# RF.net
KiCad netlist of a schematic drawn in Altium Designer
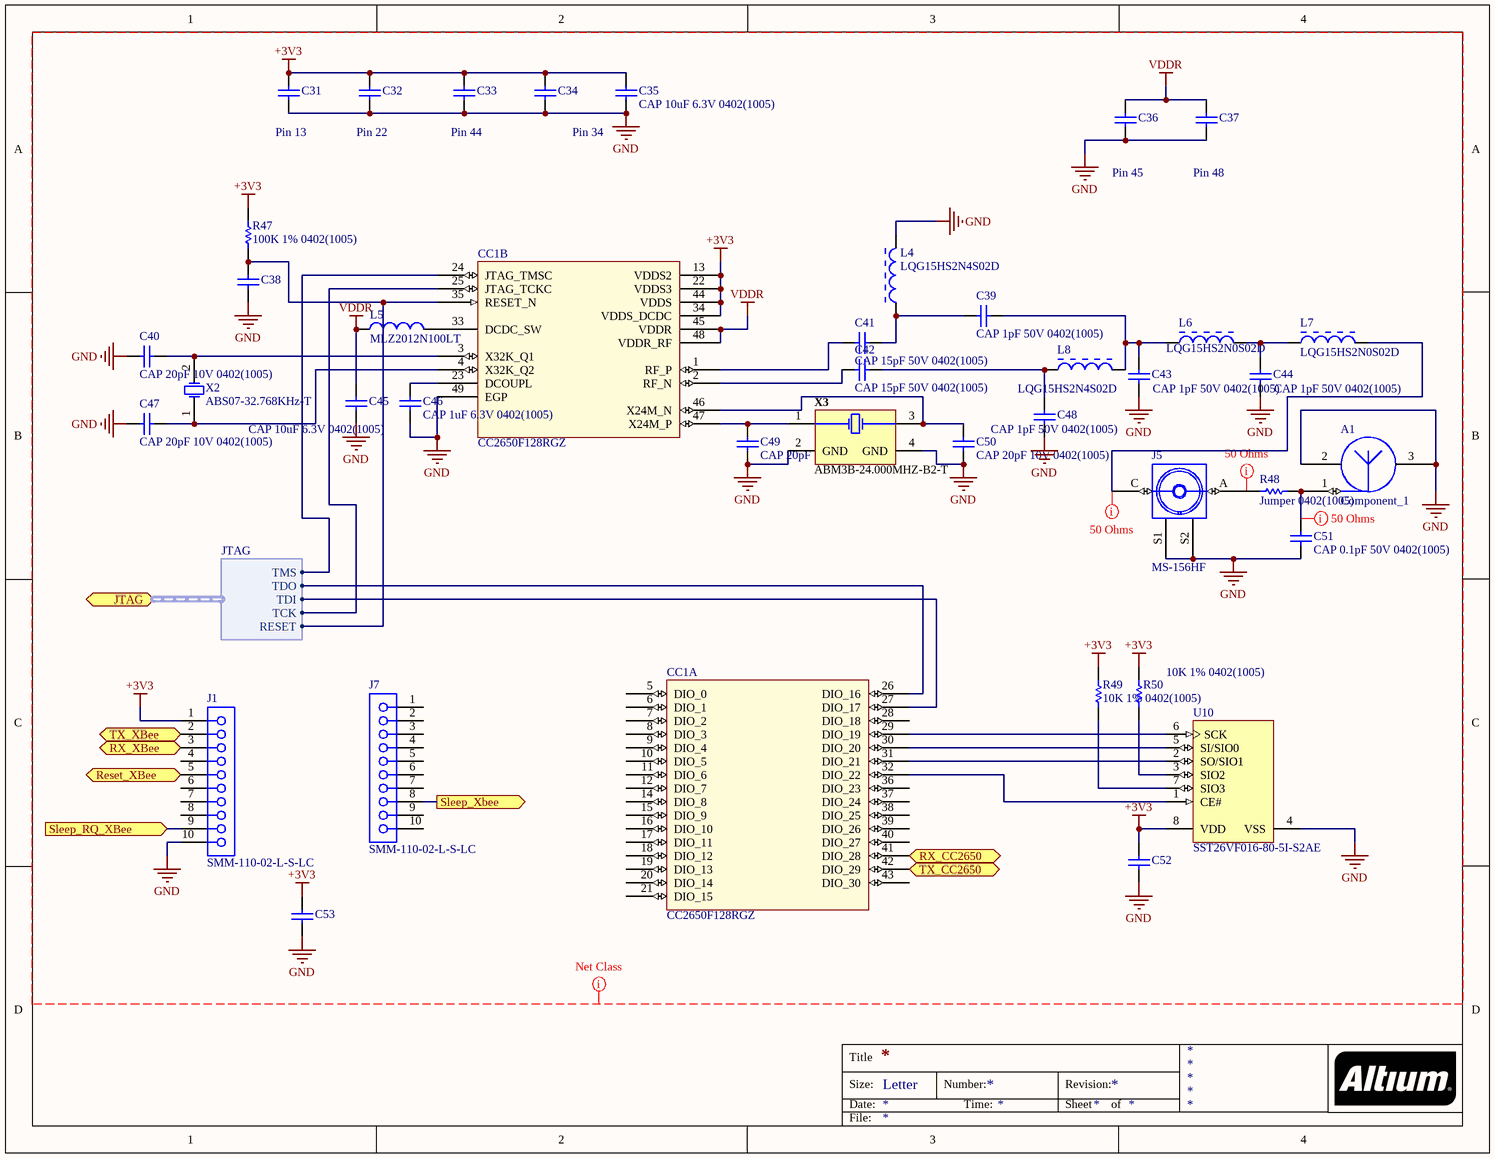
[diagram p0: RF.SchDoc]

(export (version "E")
  (design (tool "Eeschema 10.0.6"))
  (components
    (comp (ref "A1")
      (value "Component_1")
      (footprint "Microstrip Antenna")
      (libsource (lib "Antenna") (part "Component_1"))
    )
    (comp (ref "C31")
      (value "CAP 100nF 10V 0402(1005)")
      (footprint "CAPC0402(1005)60_L")
      (description "CAP 100nF 10V ±20% 0402 (1005 Metric) Thickness 0.6mm SMD")
      (fields (field (name "TOLERANCE") "Â±20%"))
      (libsource (lib "Altium Content Vault") (part "CAP"))
    )
    (comp (ref "C32")
      (value "CAP 100nF 10V 0402(1005)")
      (footprint "CAPC0402(1005)60_L")
      (description "CAP 100nF 10V ±20% 0402 (1005 Metric) Thickness 0.6mm SMD")
      (fields (field (name "TOLERANCE") "Â±20%"))
      (libsource (lib "Altium Content Vault") (part "CAP"))
    )
    (comp (ref "C33")
      (value "CAP 100nF 10V 0402(1005)")
      (footprint "CAPC0402(1005)60_L")
      (description "CAP 100nF 10V ±20% 0402 (1005 Metric) Thickness 0.6mm SMD")
      (fields (field (name "TOLERANCE") "Â±20%"))
      (libsource (lib "Altium Content Vault") (part "CAP"))
    )
    (comp (ref "C34")
      (value "CAP 100nF 10V 0402(1005)")
      (footprint "CAPC0402(1005)60_L")
      (description "CAP 100nF 10V ±20% 0402 (1005 Metric) Thickness 0.6mm SMD")
      (fields (field (name "TOLERANCE") "Â±20%"))
      (libsource (lib "Altium Content Vault") (part "CAP"))
    )
    (comp (ref "C35")
      (value "CAP 10uF 6.3V 0402(1005)")
      (footprint "CAPC0402(1005)60_L")
      (description "CAP 10uF 6.3V ±20% 0402 (1005 Metric) Thickness 0.6mm SMD")
      (fields (field (name "TOLERANCE") "Â±20%"))
      (libsource (lib "Altium Content Vault") (part "CAP"))
    )
    (comp (ref "C36")
      (value "CAP 100nF 10V 0402(1005)")
      (footprint "CAPC0402(1005)60_L")
      (description "CAP 100nF 10V ±20% 0402 (1005 Metric) Thickness 0.6mm SMD")
      (fields (field (name "TOLERANCE") "Â±20%"))
      (libsource (lib "Altium Content Vault") (part "CAP"))
    )
    (comp (ref "C37")
      (value "CAP 100nF 10V 0402(1005)")
      (footprint "CAPC0402(1005)60_L")
      (description "CAP 100nF 10V ±20% 0402 (1005 Metric) Thickness 0.6mm SMD")
      (fields (field (name "TOLERANCE") "Â±20%"))
      (libsource (lib "Altium Content Vault") (part "CAP"))
    )
    (comp (ref "C38")
      (value "CAP 100nF 10V 0402(1005)")
      (footprint "CAPC0402(1005)60_L")
      (description "CAP 100nF 10V ±20% 0402 (1005 Metric) Thickness 0.6mm SMD")
      (fields (field (name "TOLERANCE") "Â±20%"))
      (libsource (lib "Altium Content Vault") (part "CAP"))
    )
    (comp (ref "C39")
      (value "CAP 1pF 50V 0402(1005)")
      (footprint "CAPC0402(1005)33_L")
      (description "CAP 1pF 50V ±0.25pF 0402 (1005 Metric) Thickness 0.33mm SMD")
      (fields (field (name "TOLERANCE") "Â±0.25pF"))
      (libsource (lib "Altium Content Vault") (part "CMP-1034-00058-1"))
    )
    (comp (ref "C40")
      (value "CAP 20pF 10V 0402(1005)")
      (footprint "CAPC0402(1005)60_L")
      (description "CAP 20pF 10V ±5% 0402 (1005 Metric) Thickness 0.6mm SMD")
      (fields (field (name "TOLERANCE") "Â±5%"))
      (libsource (lib "Altium Content Vault") (part "CAP"))
    )
    (comp (ref "C41")
      (value "CAP 15pF 50V 0402(1005)")
      (footprint "CAPC0402(1005)33_L")
      (description "CAP 15pF 50V ±5% 0402 (1005 Metric) Thickness 0.33mm SMD")
      (fields (field (name "TOLERANCE") "Â±5%"))
      (libsource (lib "Altium Content Vault") (part "CMP-1034-00814-1"))
    )
    (comp (ref "C42")
      (value "CAP 15pF 50V 0402(1005)")
      (footprint "CAPC0402(1005)33_L")
      (description "CAP 15pF 50V ±5% 0402 (1005 Metric) Thickness 0.33mm SMD")
      (fields (field (name "TOLERANCE") "Â±5%"))
      (libsource (lib "Altium Content Vault") (part "CMP-1034-00814-1"))
    )
    (comp (ref "C43")
      (value "CAP 1pF 50V 0402(1005)")
      (footprint "CAPC0402(1005)33_L")
      (description "CAP 1pF 50V ±0.25pF 0402 (1005 Metric) Thickness 0.33mm SMD")
      (fields (field (name "TOLERANCE") "Â±0.25pF"))
      (libsource (lib "Altium Content Vault") (part "CMP-1034-00058-1"))
    )
    (comp (ref "C44")
      (value "CAP 1pF 50V 0402(1005)")
      (footprint "CAPC0402(1005)33_L")
      (description "CAP 1pF 50V ±0.25pF 0402 (1005 Metric) Thickness 0.33mm SMD")
      (fields (field (name "TOLERANCE") "Â±0.25pF"))
      (libsource (lib "Altium Content Vault") (part "CMP-1034-00058-1"))
    )
    (comp (ref "C45")
      (value "CAP 10uF 6.3V 0402(1005)")
      (footprint "CAPC0402(1005)60_L")
      (description "CAP 10uF 6.3V ±20% 0402 (1005 Metric) Thickness 0.6mm SMD")
      (fields (field (name "TOLERANCE") "Â±20%"))
      (libsource (lib "Altium Content Vault") (part "CMP-1034-02138-1"))
    )
    (comp (ref "C46")
      (value "CAP 1uF 6.3V 0402(1005)")
      (footprint "CAPC0402(1005)60_L")
      (description "CAP 1uF 6.3V -20% to +80% 0402 (1005 Metric) Thickness 0.6mm SMD")
      (fields (field (name "TOLERANCE") "-20% to +80%"))
      (libsource (lib "Altium Content Vault") (part "CAP"))
    )
    (comp (ref "C47")
      (value "CAP 20pF 10V 0402(1005)")
      (footprint "CAPC0402(1005)60_L")
      (description "CAP 20pF 10V ±5% 0402 (1005 Metric) Thickness 0.6mm SMD")
      (fields (field (name "TOLERANCE") "Â±5%"))
      (libsource (lib "Altium Content Vault") (part "CAP"))
    )
    (comp (ref "C48")
      (value "CAP 1pF 50V 0402(1005)")
      (footprint "CAPC0402(1005)33_L")
      (description "CAP 1pF 50V ±0.25pF 0402 (1005 Metric) Thickness 0.33mm SMD")
      (fields (field (name "TOLERANCE") "Â±0.25pF"))
      (libsource (lib "Altium Content Vault") (part "CMP-1034-00058-1"))
    )
    (comp (ref "C49")
      (value "CAP 20pF 10V 0402(1005)")
      (footprint "CAPC0402(1005)60_L")
      (description "CAP 20pF 10V ±5% 0402 (1005 Metric) Thickness 0.6mm SMD")
      (fields (field (name "TOLERANCE") "Â±5%"))
      (libsource (lib "Altium Content Vault") (part "CMP-1034-00874-1"))
    )
    (comp (ref "C50")
      (value "CAP 20pF 10V 0402(1005)")
      (footprint "CAPC0402(1005)60_L")
      (description "CAP 20pF 10V ±5% 0402 (1005 Metric) Thickness 0.6mm SMD")
      (fields (field (name "TOLERANCE") "Â±5%"))
      (libsource (lib "Altium Content Vault") (part "CMP-1034-00874-1"))
    )
    (comp (ref "C51")
      (value "CAP 0.1pF 50V 0402(1005)")
      (footprint "CAPC0402(1005)33_L")
      (description "CAP 0.1pF 50V ±0.1pF 0402 (1005 Metric) Thickness 0.33mm SMD")
      (fields (field (name "TOLERANCE") "Â±0.1pF"))
      (libsource (lib "Altium Content Vault") (part "CMP-1034-00002-1"))
    )
    (comp (ref "C52")
      (value "CAP 100nF 10V 0402(1005)")
      (footprint "CAPC0402(1005)60_L")
      (description "CAP 100nF 10V ±20% 0402 (1005 Metric) Thickness 0.6mm SMD")
      (fields (field (name "TOLERANCE") "Â±20%"))
      (libsource (lib "Altium Content Vault") (part "CAP"))
    )
    (comp (ref "C53")
      (value "CAP 100nF 10V 0402(1005)")
      (footprint "CAPC0402(1005)60_L")
      (description "CAP 100nF 10V ±20% 0402 (1005 Metric) Thickness 0.6mm SMD")
      (fields (field (name "TOLERANCE") "Â±20%"))
      (libsource (lib "Altium Content Vault") (part "CMP-1034-02066-1"))
    )
    (comp (ref "CC1")
      (value "CC2650F128RGZ")
      (footprint "RGZ48-4100X4100TP")
      (description "RF Microcontrollers - MCU SimpleLink multi-std Wireless MCU 2.4Ghz")
      (fields
        (field (name "MANUFACTURER") "Texas Instruments")
        (field (name "MANUFACTURER PART NUMBER") "CC2650F128RGZT")
      )
      (libsource (lib "CERN PCB Vault") (part "CC2650 7x7"))
    )
    (comp (ref "J1")
      (value "SMM-110-02-L-S-LC")
      (footprint "SMTC-SMM-110-02-X-S-LC")
      (fields (field (name "MANUFACTURER") "Samtec"))
      (libsource (lib "Altium Content Vault") (part "CMP-1022-00175-1"))
    )
    (comp (ref "J5")
      (value "MS-156HF")
      (footprint "MS-156HF")
      (description "Subminiature Coaxial Swtich, 1.6mm High, DC - 6GHz")
      (libsource (lib "MS-156HF") (part "MS-156HF"))
    )
    (comp (ref "J7")
      (value "SMM-110-02-L-S-LC")
      (footprint "SMTC-SMM-110-02-X-S-LC")
      (fields (field (name "MANUFACTURER") "Samtec"))
      (libsource (lib "Altium Content Vault") (part "CMP-1022-00175-1"))
    )
    (comp (ref "L4")
      (value "LQG15HS2N4S02D")
      (footprint "MURA-IND0402_V")
      (fields (field (name "MANUFACTURER") "Murata"))
      (libsource (lib "Altium Content Vault") (part "CMP-0499-00001-3"))
    )
    (comp (ref "L5")
      (value "MLZ2012N100LT")
      (footprint "TDK-IND0805-125_V")
      (description "Multilayer Inductor, 10 uH, ±20%, 300 mOhm, 50MHz, 0805(2012)")
      (libsource (lib "Altium Content Vault") (part "CMP-0266-00001-1"))
    )
    (comp (ref "L6")
      (value "LQG15HS2N0S02D")
      (footprint "MURA-IND0402_V")
      (fields (field (name "MANUFACTURER") "Murata"))
      (libsource (lib "Altium Content Vault") (part "MURA-INDC-2"))
    )
    (comp (ref "L7")
      (value "LQG15HS2N0S02D")
      (footprint "MURA-IND0402_V")
      (fields (field (name "MANUFACTURER") "Murata"))
      (libsource (lib "Altium Content Vault") (part "MURA-INDC-2"))
    )
    (comp (ref "L8")
      (value "LQG15HS2N4S02D")
      (footprint "MURA-IND0402_V")
      (fields (field (name "MANUFACTURER") "Murata"))
      (libsource (lib "Altium Content Vault") (part "CMP-0499-00001-3"))
    )
    (comp (ref "R47")
      (value "100K 1% 0402(1005)")
      (footprint "RESC0402(1005)_L")
      (description "100K 0.063W 1% 0402 (1005 Metric)  SMD")
      (fields (field (name "POWER") "0.063 W") (field (name "TOLERANCE") "1 %"))
      (libsource (lib "Altium Content Vault") (part "RES"))
    )
    (comp (ref "R48")
      (value "Jumper 0402(1005)")
      (footprint "RESC0402(1005)_L")
      (description "Jumper 0402 (1005 Metric)")
      (fields (field (name "TOLERANCE") "None"))
      (libsource (lib "Altium Content Vault") (part "RES"))
    )
    (comp (ref "R49")
      (value "10K 1% 0402(1005)")
      (footprint "RESC0402(1005)_L")
      (description "10K 0.063W 1% 0402 (1005 Metric)  SMD")
      (fields (field (name "TOLERANCE") "1 %") (field (name "POWER") "0.063 W"))
      (libsource (lib "Altium Content Vault") (part "RES"))
    )
    (comp (ref "R50")
      (value "10K 1% 0402(1005)")
      (footprint "RESC0402(1005)_L")
      (description "10K 0.063W 1% 0402 (1005 Metric)  SMD")
      (fields (field (name "TOLERANCE") "1 %") (field (name "POWER") "0.063 W"))
      (libsource (lib "Altium Content Vault") (part "RES"))
    )
    (comp (ref "U10")
      (value "SST26VF016-80-5I-S2AE")
      (footprint "MCHP-SOIC-S2A8_L")
      (fields (field (name "MANUFACTURER") "Microchip"))
      (libsource (lib "Altium Content Vault") (part "MCHP-SST26VFXXX-SOIJ-8"))
    )
    (comp (ref "X2")
      (value "ABS07-32.768KHz-T")
      (footprint "ABRA-ABS07-2_V")
      (description "Crystal, 32.768 kHz, 12.5 pF, -40 to 85 degC, SMD Low Profile 3.2 x 1.5 x 0.9 mm, Tape and Reel")
      (fields (field (name "MANUFACTURER") "Abracon"))
      (libsource (lib "Altium Content Vault") (part "CMP-0447-00001-2"))
    )
    (comp (ref "X3")
      (value "ABM3B-24.000MHZ-B2-T")
      (footprint "ABRA-ABM3B-4_V")
      (description "Ceramic SMD Crystal, 24 MHz, +/- 20 ppm, 50 Ohm, -20 to 70 degC, 4-Pin SMD, RoHS, Tape and Reel")
      (libsource (lib "Altium Content Vault") (part "CMP-1688-00008-1"))
    )
  )
  (nets
    (net (code "2") (name "+3V3") (class "Default")
      (node (ref "C31") (pin "2") (pinfunction "2_2") (pintype "passive"))
      (node (ref "C32") (pin "2") (pinfunction "2_2") (pintype "passive"))
      (node (ref "C33") (pin "2") (pinfunction "2_2") (pintype "passive"))
      (node (ref "C34") (pin "2") (pinfunction "2_2") (pintype "passive"))
      (node (ref "C35") (pin "2") (pinfunction "2_2") (pintype "passive"))
      (node (ref "C52") (pin "2") (pinfunction "2_2") (pintype "passive"))
      (node (ref "C53") (pin "2") (pinfunction "2_2") (pintype "passive"))
      (node (ref "CC1") (pin "13") (pinfunction "VDDS2_13") (pintype "power_in"))
      (node (ref "CC1") (pin "22") (pinfunction "VDDS3_22") (pintype "power_in"))
      (node (ref "CC1") (pin "34") (pinfunction "VDDS_DCDC_34") (pintype "power_in"))
      (node (ref "CC1") (pin "44") (pinfunction "VDDS_44") (pintype "power_in"))
      (node (ref "J1") (pin "1") (pinfunction "1_1") (pintype "passive"))
      (node (ref "R47") (pin "2") (pinfunction "2_2") (pintype "passive"))
      (node (ref "R49") (pin "2") (pinfunction "2_2") (pintype "passive"))
      (node (ref "R50") (pin "2") (pinfunction "2_2") (pintype "passive"))
      (node (ref "U10") (pin "8") (pinfunction "VDD_8") (pintype "power_in"))
    )
    (net (code "3") (name "/RESET") (class "Default")
      (node (ref "C38") (pin "2") (pinfunction "2_2") (pintype "passive"))
      (node (ref "CC1") (pin "35") (pinfunction "RESET_N_35") (pintype "input"))
      (node (ref "R47") (pin "1") (pinfunction "1_1") (pintype "passive"))
    )
    (net (code "4") (name "/RX_CC2650") (class "Default")
      (node (ref "CC1") (pin "41") (pinfunction "DIO_28_41") (pintype "bidirectional"))
    )
    (net (code "5") (name "/RX_XBee") (class "Default")
      (node (ref "J1") (pin "3") (pinfunction "3_3") (pintype "passive"))
    )
    (net (code "6") (name "/Reset_XBee") (class "Default")
      (node (ref "J1") (pin "5") (pinfunction "5_5") (pintype "passive"))
    )
    (net (code "7") (name "/Sleep_RQ_XBee") (class "Default")
      (node (ref "J1") (pin "9") (pinfunction "9_9") (pintype "passive"))
    )
    (net (code "8") (name "/Sleep_Xbee") (class "Default")
      (node (ref "J7") (pin "8") (pinfunction "8_8") (pintype "passive"))
    )
    (net (code "9") (name "/TCK") (class "Default")
      (node (ref "CC1") (pin "25") (pinfunction "JTAG_TCKC_25") (pintype "bidirectional"))
    )
    (net (code "10") (name "/TDI") (class "Default")
      (node (ref "CC1") (pin "27") (pinfunction "DIO_17_27") (pintype "bidirectional"))
    )
    (net (code "11") (name "/TDO") (class "Default")
      (node (ref "CC1") (pin "26") (pinfunction "DIO_16_26") (pintype "bidirectional"))
    )
    (net (code "12") (name "/TMS") (class "Default")
      (node (ref "CC1") (pin "24") (pinfunction "JTAG_TMSC_24") (pintype "bidirectional"))
    )
    (net (code "13") (name "/TX_CC2650") (class "Default")
      (node (ref "CC1") (pin "42") (pinfunction "DIO_29_42") (pintype "bidirectional"))
    )
    (net (code "14") (name "/TX_XBee") (class "Default")
      (node (ref "J1") (pin "2") (pinfunction "2_2") (pintype "passive"))
    )
    (net (code "16") (name "GND") (class "Default")
      (node (ref "A1") (pin "2") (pinfunction "2_2") (pintype "power_in"))
      (node (ref "A1") (pin "3") (pinfunction "3_3") (pintype "power_in"))
      (node (ref "C31") (pin "1") (pinfunction "1_1") (pintype "passive"))
      (node (ref "C32") (pin "1") (pinfunction "1_1") (pintype "passive"))
      (node (ref "C33") (pin "1") (pinfunction "1_1") (pintype "passive"))
      (node (ref "C34") (pin "1") (pinfunction "1_1") (pintype "passive"))
      (node (ref "C35") (pin "1") (pinfunction "1_1") (pintype "passive"))
      (node (ref "C36") (pin "1") (pinfunction "1_1") (pintype "passive"))
      (node (ref "C37") (pin "1") (pinfunction "1_1") (pintype "passive"))
      (node (ref "C38") (pin "1") (pinfunction "1_1") (pintype "passive"))
      (node (ref "C40") (pin "1") (pinfunction "1_1") (pintype "passive"))
      (node (ref "C43") (pin "1") (pinfunction "1_1") (pintype "passive"))
      (node (ref "C44") (pin "1") (pinfunction "1_1") (pintype "passive"))
      (node (ref "C45") (pin "1") (pinfunction "1_1") (pintype "passive"))
      (node (ref "C46") (pin "1") (pinfunction "1_1") (pintype "passive"))
      (node (ref "C47") (pin "1") (pinfunction "1_1") (pintype "passive"))
      (node (ref "C48") (pin "1") (pinfunction "1_1") (pintype "passive"))
      (node (ref "C49") (pin "2") (pinfunction "2_2") (pintype "passive"))
      (node (ref "C50") (pin "2") (pinfunction "2_2") (pintype "passive"))
      (node (ref "C51") (pin "1") (pinfunction "1_1") (pintype "passive"))
      (node (ref "C52") (pin "1") (pinfunction "1_1") (pintype "passive"))
      (node (ref "C53") (pin "1") (pinfunction "1_1") (pintype "passive"))
      (node (ref "CC1") (pin "49") (pinfunction "EGP_49") (pintype "power_in"))
      (node (ref "J1") (pin "10") (pinfunction "10_10") (pintype "passive"))
      (node (ref "J5") (pin "S1") (pinfunction "S1_S1") (pintype "power_in"))
      (node (ref "J5") (pin "S2") (pinfunction "S2_S2") (pintype "power_in"))
      (node (ref "L4") (pin "2") (pinfunction "2_2") (pintype "passive"))
      (node (ref "U10") (pin "4") (pinfunction "VSS_4") (pintype "power_in"))
      (node (ref "X3") (pin "2") (pinfunction "GND_2") (pintype "power_in"))
      (node (ref "X3") (pin "4") (pinfunction "GND_4") (pintype "power_in"))
    )
    (net (code "17") (name "Net-(A1-Pad1)") (class "Default")
      (node (ref "A1") (pin "1") (pinfunction "1_1") (pintype "bidirectional"))
      (node (ref "C51") (pin "2") (pinfunction "2_2") (pintype "passive"))
      (node (ref "R48") (pin "2") (pinfunction "2_2") (pintype "passive"))
    )
    (net (code "18") (name "Net-(C39-Pad1)") (class "Default")
      (node (ref "C39") (pin "1") (pinfunction "1_1") (pintype "passive"))
      (node (ref "C41") (pin "2") (pinfunction "2_2") (pintype "passive"))
      (node (ref "L4") (pin "1") (pinfunction "1_1") (pintype "passive"))
    )
    (net (code "19") (name "Net-(C39-Pad2)") (class "Default")
      (node (ref "C39") (pin "2") (pinfunction "2_2") (pintype "passive"))
      (node (ref "C43") (pin "2") (pinfunction "2_2") (pintype "passive"))
      (node (ref "L6") (pin "1") (pinfunction "1_1") (pintype "passive"))
      (node (ref "L8") (pin "2") (pinfunction "2_2") (pintype "passive"))
    )
    (net (code "20") (name "Net-(C42-Pad2)") (class "Default")
      (node (ref "C42") (pin "2") (pinfunction "2_2") (pintype "passive"))
      (node (ref "C48") (pin "2") (pinfunction "2_2") (pintype "passive"))
      (node (ref "L8") (pin "1") (pinfunction "1_1") (pintype "passive"))
    )
    (net (code "21") (name "Net-(C44-Pad2)") (class "Default")
      (node (ref "C44") (pin "2") (pinfunction "2_2") (pintype "passive"))
      (node (ref "L6") (pin "2") (pinfunction "2_2") (pintype "passive"))
      (node (ref "L7") (pin "1") (pinfunction "1_1") (pintype "passive"))
    )
    (net (code "22") (name "Net-(CC1A-DIO_19)") (class "Default")
      (node (ref "CC1") (pin "29") (pinfunction "DIO_19_29") (pintype "bidirectional"))
      (node (ref "U10") (pin "6") (pinfunction "SCK_6") (pintype "input"))
    )
    (net (code "23") (name "Net-(CC1A-DIO_20)") (class "Default")
      (node (ref "CC1") (pin "30") (pinfunction "DIO_20_30") (pintype "bidirectional"))
      (node (ref "U10") (pin "5") (pinfunction "SI/SIO0_5") (pintype "bidirectional"))
    )
    (net (code "24") (name "Net-(CC1A-DIO_21)") (class "Default")
      (node (ref "CC1") (pin "31") (pinfunction "DIO_21_31") (pintype "bidirectional"))
      (node (ref "U10") (pin "2") (pinfunction "SO/SIO1_2") (pintype "bidirectional"))
    )
    (net (code "25") (name "Net-(CC1A-DIO_22)") (class "Default")
      (node (ref "CC1") (pin "32") (pinfunction "DIO_22_32") (pintype "bidirectional"))
      (node (ref "U10") (pin "1") (pinfunction "CE#_1") (pintype "input"))
    )
    (net (code "26") (name "Net-(CC1B-DCDC_SW)") (class "Default")
      (node (ref "CC1") (pin "33") (pinfunction "DCDC_SW_33") (pintype "power_in"))
      (node (ref "L5") (pin "2") (pinfunction "2_2") (pintype "passive"))
    )
    (net (code "27") (name "Net-(CC1B-DCOUPL)") (class "Default")
      (node (ref "C46") (pin "2") (pinfunction "2_2") (pintype "passive"))
      (node (ref "CC1") (pin "23") (pinfunction "DCOUPL_23") (pintype "power_in"))
    )
    (net (code "28") (name "Net-(CC1B-RF_N)") (class "Default")
      (node (ref "C42") (pin "1") (pinfunction "1_1") (pintype "passive"))
      (node (ref "CC1") (pin "2") (pinfunction "RF_N_2") (pintype "bidirectional"))
    )
    (net (code "29") (name "Net-(CC1B-RF_P)") (class "Default")
      (node (ref "C41") (pin "1") (pinfunction "1_1") (pintype "passive"))
      (node (ref "CC1") (pin "1") (pinfunction "RF_P_1") (pintype "bidirectional"))
    )
    (net (code "30") (name "Net-(CC1B-X24M_N)") (class "Default")
      (node (ref "C50") (pin "1") (pinfunction "1_1") (pintype "passive"))
      (node (ref "CC1") (pin "46") (pinfunction "X24M_N_46") (pintype "bidirectional"))
      (node (ref "X3") (pin "3") (pinfunction "X2_3") (pintype "passive"))
    )
    (net (code "31") (name "Net-(CC1B-X24M_P)") (class "Default")
      (node (ref "C49") (pin "1") (pinfunction "1_1") (pintype "passive"))
      (node (ref "CC1") (pin "47") (pinfunction "X24M_P_47") (pintype "bidirectional"))
      (node (ref "X3") (pin "1") (pinfunction "X1_1") (pintype "passive"))
    )
    (net (code "32") (name "Net-(CC1B-X32K_Q1)") (class "Default")
      (node (ref "C40") (pin "2") (pinfunction "2_2") (pintype "passive"))
      (node (ref "CC1") (pin "3") (pinfunction "X32K_Q1_3") (pintype "bidirectional"))
      (node (ref "X2") (pin "2") (pinfunction "X2_2") (pintype "passive"))
    )
    (net (code "33") (name "Net-(CC1B-X32K_Q2)") (class "Default")
      (node (ref "C47") (pin "2") (pinfunction "2_2") (pintype "passive"))
      (node (ref "CC1") (pin "4") (pinfunction "X32K_Q2_4") (pintype "bidirectional"))
      (node (ref "X2") (pin "1") (pinfunction "X1_1") (pintype "passive"))
    )
    (net (code "34") (name "Net-(J5-PadA)") (class "Default")
      (node (ref "J5") (pin "A") (pinfunction "A_A") (pintype "bidirectional"))
      (node (ref "R48") (pin "1") (pinfunction "1_1") (pintype "passive"))
    )
    (net (code "35") (name "Net-(J5-PadC)") (class "Default")
      (node (ref "J5") (pin "C") (pinfunction "C_C") (pintype "bidirectional"))
      (node (ref "L7") (pin "2") (pinfunction "2_2") (pintype "passive"))
    )
    (net (code "36") (name "Net-(U10-SIO2)") (class "Default")
      (node (ref "R50") (pin "1") (pinfunction "1_1") (pintype "passive"))
      (node (ref "U10") (pin "3") (pinfunction "SIO2_3") (pintype "bidirectional"))
    )
    (net (code "37") (name "Net-(U10-SIO3)") (class "Default")
      (node (ref "R49") (pin "1") (pinfunction "1_1") (pintype "passive"))
      (node (ref "U10") (pin "7") (pinfunction "SIO3_7") (pintype "bidirectional"))
    )
    (net (code "38") (name "VDDR") (class "Default")
      (node (ref "C36") (pin "2") (pinfunction "2_2") (pintype "passive"))
      (node (ref "C37") (pin "2") (pinfunction "2_2") (pintype "passive"))
      (node (ref "C45") (pin "2") (pinfunction "2_2") (pintype "passive"))
      (node (ref "CC1") (pin "45") (pinfunction "VDDR_45") (pintype "power_in"))
      (node (ref "CC1") (pin "48") (pinfunction "VDDR_RF_48") (pintype "power_in"))
      (node (ref "L5") (pin "1") (pinfunction "1_1") (pintype "passive"))
    )
    (net (code "39") (name "unconnected-(CC1A-DIO_0-Pad5)") (class "Default")
      (node (ref "CC1") (pin "5") (pinfunction "DIO_0_5") (pintype "bidirectional"))
    )
    (net (code "40") (name "unconnected-(CC1A-DIO_1-Pad6)") (class "Default")
      (node (ref "CC1") (pin "6") (pinfunction "DIO_1_6") (pintype "bidirectional"))
    )
    (net (code "41") (name "unconnected-(CC1A-DIO_2-Pad7)") (class "Default")
      (node (ref "CC1") (pin "7") (pinfunction "DIO_2_7") (pintype "bidirectional"))
    )
    (net (code "42") (name "unconnected-(CC1A-DIO_3-Pad8)") (class "Default")
      (node (ref "CC1") (pin "8") (pinfunction "DIO_3_8") (pintype "bidirectional"))
    )
    (net (code "43") (name "unconnected-(CC1A-DIO_4-Pad9)") (class "Default")
      (node (ref "CC1") (pin "9") (pinfunction "DIO_4_9") (pintype "bidirectional"))
    )
    (net (code "44") (name "unconnected-(CC1A-DIO_5-Pad10)") (class "Default")
      (node (ref "CC1") (pin "10") (pinfunction "DIO_5_10") (pintype "bidirectional"))
    )
    (net (code "45") (name "unconnected-(CC1A-DIO_6-Pad11)") (class "Default")
      (node (ref "CC1") (pin "11") (pinfunction "DIO_6_11") (pintype "bidirectional"))
    )
    (net (code "46") (name "unconnected-(CC1A-DIO_7-Pad12)") (class "Default")
      (node (ref "CC1") (pin "12") (pinfunction "DIO_7_12") (pintype "bidirectional"))
    )
    (net (code "47") (name "unconnected-(CC1A-DIO_8-Pad14)") (class "Default")
      (node (ref "CC1") (pin "14") (pinfunction "DIO_8_14") (pintype "bidirectional"))
    )
    (net (code "48") (name "unconnected-(CC1A-DIO_9-Pad15)") (class "Default")
      (node (ref "CC1") (pin "15") (pinfunction "DIO_9_15") (pintype "bidirectional"))
    )
    (net (code "49") (name "unconnected-(CC1A-DIO_10-Pad16)") (class "Default")
      (node (ref "CC1") (pin "16") (pinfunction "DIO_10_16") (pintype "bidirectional"))
    )
    (net (code "50") (name "unconnected-(CC1A-DIO_11-Pad17)") (class "Default")
      (node (ref "CC1") (pin "17") (pinfunction "DIO_11_17") (pintype "bidirectional"))
    )
    (net (code "51") (name "unconnected-(CC1A-DIO_12-Pad18)") (class "Default")
      (node (ref "CC1") (pin "18") (pinfunction "DIO_12_18") (pintype "bidirectional"))
    )
    (net (code "52") (name "unconnected-(CC1A-DIO_13-Pad19)") (class "Default")
      (node (ref "CC1") (pin "19") (pinfunction "DIO_13_19") (pintype "bidirectional"))
    )
    (net (code "53") (name "unconnected-(CC1A-DIO_14-Pad20)") (class "Default")
      (node (ref "CC1") (pin "20") (pinfunction "DIO_14_20") (pintype "bidirectional"))
    )
    (net (code "54") (name "unconnected-(CC1A-DIO_15-Pad21)") (class "Default")
      (node (ref "CC1") (pin "21") (pinfunction "DIO_15_21") (pintype "bidirectional"))
    )
    (net (code "55") (name "unconnected-(CC1A-DIO_18-Pad28)") (class "Default")
      (node (ref "CC1") (pin "28") (pinfunction "DIO_18_28") (pintype "bidirectional"))
    )
    (net (code "56") (name "unconnected-(CC1A-DIO_23-Pad36)") (class "Default")
      (node (ref "CC1") (pin "36") (pinfunction "DIO_23_36") (pintype "bidirectional"))
    )
    (net (code "57") (name "unconnected-(CC1A-DIO_24-Pad37)") (class "Default")
      (node (ref "CC1") (pin "37") (pinfunction "DIO_24_37") (pintype "bidirectional"))
    )
    (net (code "58") (name "unconnected-(CC1A-DIO_25-Pad38)") (class "Default")
      (node (ref "CC1") (pin "38") (pinfunction "DIO_25_38") (pintype "bidirectional"))
    )
    (net (code "59") (name "unconnected-(CC1A-DIO_26-Pad39)") (class "Default")
      (node (ref "CC1") (pin "39") (pinfunction "DIO_26_39") (pintype "bidirectional"))
    )
    (net (code "60") (name "unconnected-(CC1A-DIO_27-Pad40)") (class "Default")
      (node (ref "CC1") (pin "40") (pinfunction "DIO_27_40") (pintype "bidirectional"))
    )
    (net (code "61") (name "unconnected-(CC1A-DIO_30-Pad43)") (class "Default")
      (node (ref "CC1") (pin "43") (pinfunction "DIO_30_43") (pintype "bidirectional"))
    )
    (net (code "62") (name "unconnected-(J1-Pad4)") (class "Default")
      (node (ref "J1") (pin "4") (pinfunction "4_4") (pintype "passive"))
    )
    (net (code "63") (name "unconnected-(J1-Pad6)") (class "Default")
      (node (ref "J1") (pin "6") (pinfunction "6_6") (pintype "passive"))
    )
    (net (code "64") (name "unconnected-(J1-Pad7)") (class "Default")
      (node (ref "J1") (pin "7") (pinfunction "7_7") (pintype "passive"))
    )
    (net (code "65") (name "unconnected-(J1-Pad8)") (class "Default")
      (node (ref "J1") (pin "8") (pinfunction "8_8") (pintype "passive"))
    )
    (net (code "66") (name "unconnected-(J7-Pad1)") (class "Default")
      (node (ref "J7") (pin "1") (pinfunction "1_1") (pintype "passive"))
    )
    (net (code "67") (name "unconnected-(J7-Pad2)") (class "Default")
      (node (ref "J7") (pin "2") (pinfunction "2_2") (pintype "passive"))
    )
    (net (code "68") (name "unconnected-(J7-Pad3)") (class "Default")
      (node (ref "J7") (pin "3") (pinfunction "3_3") (pintype "passive"))
    )
    (net (code "69") (name "unconnected-(J7-Pad4)") (class "Default")
      (node (ref "J7") (pin "4") (pinfunction "4_4") (pintype "passive"))
    )
    (net (code "70") (name "unconnected-(J7-Pad5)") (class "Default")
      (node (ref "J7") (pin "5") (pinfunction "5_5") (pintype "passive"))
    )
    (net (code "71") (name "unconnected-(J7-Pad6)") (class "Default")
      (node (ref "J7") (pin "6") (pinfunction "6_6") (pintype "passive"))
    )
    (net (code "72") (name "unconnected-(J7-Pad7)") (class "Default")
      (node (ref "J7") (pin "7") (pinfunction "7_7") (pintype "passive"))
    )
    (net (code "73") (name "unconnected-(J7-Pad9)") (class "Default")
      (node (ref "J7") (pin "9") (pinfunction "9_9") (pintype "passive"))
    )
    (net (code "74") (name "unconnected-(J7-Pad10)") (class "Default")
      (node (ref "J7") (pin "10") (pinfunction "10_10") (pintype "passive"))
    )
  )
)
